# Power_Supply.net
KiCad netlist of a schematic drawn in EAGLE
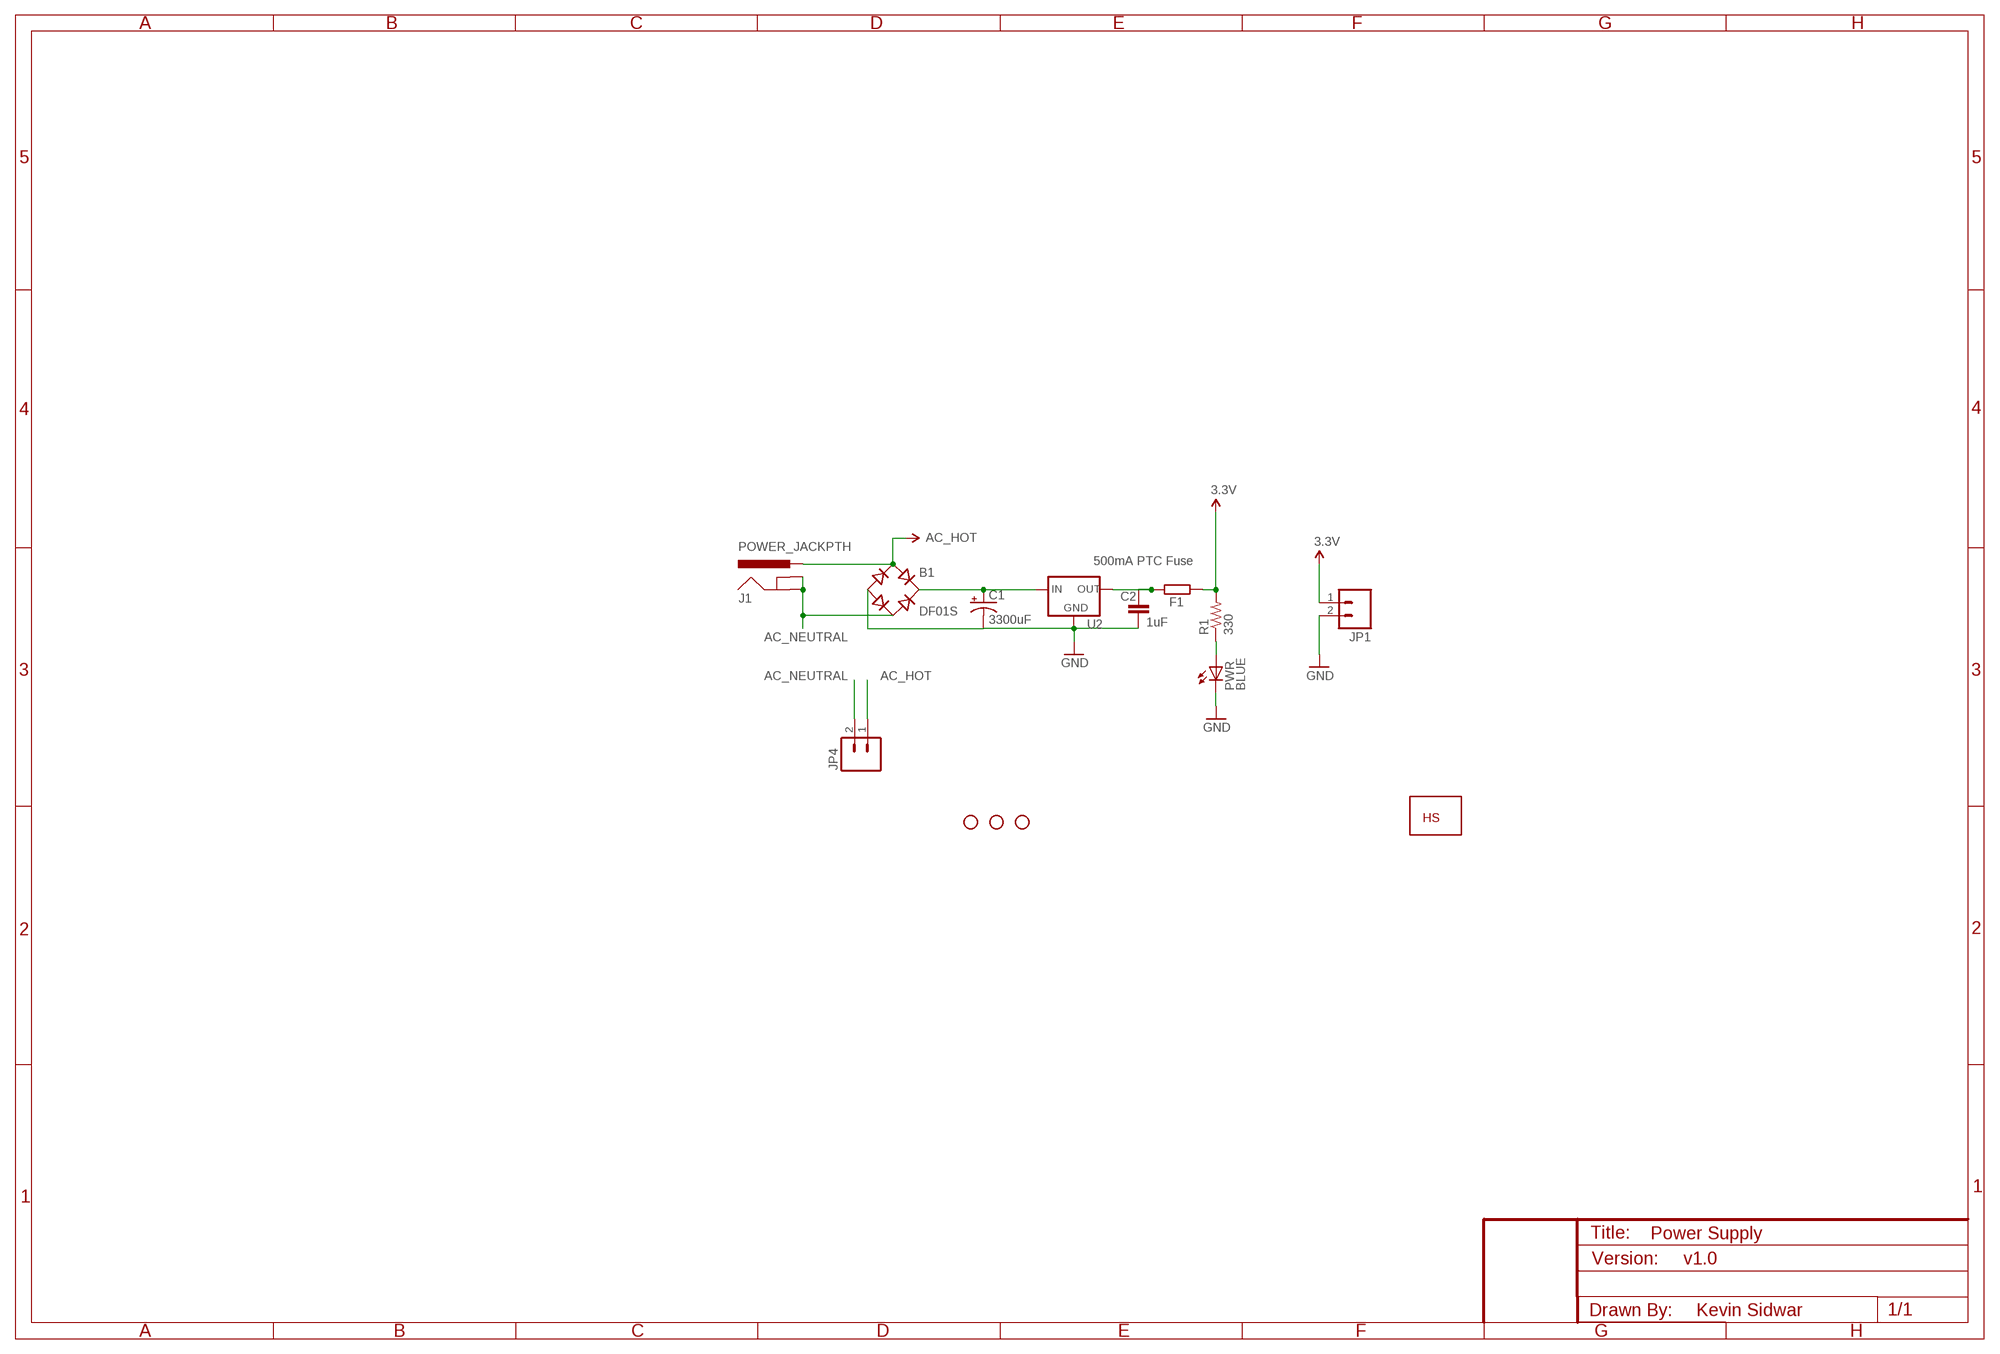
[diagram p0: schematic, sheet 1]

(export (version "E")
  (design (tool "Eeschema 10.0.6"))
  (components
    (comp (ref "B1")
      (value "DF01S")
      (footprint "eagle-import:DFS")
      (libsource (lib "eagle-import") (part "DFS01"))
    )
    (comp (ref "C1")
      (value "3300uF")
      (footprint "eagle-import:EB20D")
      (libsource (lib "eagle-import") (part "CPOL-USE10-20"))
    )
    (comp (ref "C2")
      (value "1uF")
      (footprint "eagle-import:0603-CAP")
      (libsource (lib "eagle-import") (part "CAP0603-CAP"))
    )
    (comp (ref "F1")
      (value "500mA PTC Fuse")
      (footprint "eagle-import:M1206")
      (libsource (lib "eagle-import") (part "R-EU_M1206"))
    )
    (comp (ref "J1")
      (value "POWER_JACKPTH")
      (footprint "eagle-import:POWER_JACK_PTH")
      (libsource (lib "eagle-import") (part "POWER_JACKPTH"))
    )
    (comp (ref "JP1")
      (value "M02LOCK_LONGPADS")
      (footprint "eagle-import:1X02_LOCK_LONGPADS")
      (libsource (lib "eagle-import") (part "M02LOCK_LONGPADS"))
    )
    (comp (ref "JP4")
      (value "M02LOCK_LONGPADS")
      (footprint "eagle-import:1X02_LOCK_LONGPADS")
      (libsource (lib "eagle-import") (part "M02LOCK_LONGPADS"))
    )
    (comp (ref "JP5")
      (value "STAND-OFF")
      (footprint "eagle-import:STAND-OFF")
      (libsource (lib "eagle-import") (part "STAND-OFF"))
    )
    (comp (ref "JP6")
      (value "STAND-OFF")
      (footprint "eagle-import:STAND-OFF")
      (libsource (lib "eagle-import") (part "STAND-OFF"))
    )
    (comp (ref "JP8")
      (value "STAND-OFF")
      (footprint "eagle-import:STAND-OFF")
      (libsource (lib "eagle-import") (part "STAND-OFF"))
    )
    (comp (ref "PWR")
      (value "BLUE")
      (footprint "eagle-import:LED-0603")
      (libsource (lib "eagle-import") (part "LED0603"))
    )
    (comp (ref "R1")
      (value "330")
      (footprint "eagle-import:0603-RES")
      (libsource (lib "eagle-import") (part "RESISTOR0603-RES"))
    )
    (comp (ref "U$1")
      (value "LOGONORMAL")
      (footprint "eagle-import:HS_LOGO")
      (libsource (lib "eagle-import") (part "LOGONORMAL"))
    )
    (comp (ref "U2")
      (value "RECOM_X.X_REG78XX")
      (footprint "eagle-import:RECOM")
      (libsource (lib "eagle-import") (part "RECOM_X.X_REG78XX"))
    )
  )
  (nets
    (net (code "1") (name "/AC_NEUTRAL") (class "Default")
      (node (ref "B1") (pin "AC2") (pinfunction "AC2_AC2") (pintype "passive"))
      (node (ref "J1") (pin "GND") (pinfunction "GND_GND") (pintype "bidirectional"))
      (node (ref "J1") (pin "GNDBREAK") (pinfunction "GNDBREAK_GNDBREAK") (pintype "bidirectional"))
      (node (ref "JP4") (pin "2") (pinfunction "2_2") (pintype "passive"))
    )
    (net (code "2") (name "3.3V") (class "Default")
      (node (ref "F1") (pin "1") (pinfunction "1_1") (pintype "passive"))
      (node (ref "JP1") (pin "1") (pinfunction "1_1") (pintype "passive"))
      (node (ref "R1") (pin "2") (pinfunction "2_2") (pintype "passive"))
    )
    (net (code "3") (name "AC_HOT") (class "Default")
      (node (ref "B1") (pin "AC1") (pinfunction "AC1_AC1") (pintype "passive"))
      (node (ref "J1") (pin "PWR") (pinfunction "PWR_PWR") (pintype "bidirectional"))
      (node (ref "JP4") (pin "1") (pinfunction "1_1") (pintype "passive"))
    )
    (net (code "4") (name "GND") (class "Default")
      (node (ref "B1") (pin "-") (pinfunction "-_-") (pintype "passive"))
      (node (ref "C1") (pin "-") (pinfunction "-_-") (pintype "passive"))
      (node (ref "C2") (pin "2") (pinfunction "2_2") (pintype "passive"))
      (node (ref "JP1") (pin "2") (pinfunction "2_2") (pintype "passive"))
      (node (ref "PWR") (pin "C") (pinfunction "C_C") (pintype "passive"))
      (node (ref "U2") (pin "GND") (pinfunction "GND_GND") (pintype "input"))
    )
    (net (code "5") (name "Net-(PWR-PadA)") (class "Default")
      (node (ref "PWR") (pin "A") (pinfunction "A_A") (pintype "passive"))
      (node (ref "R1") (pin "1") (pinfunction "1_1") (pintype "passive"))
    )
    (net (code "6") (name "Net-(U2-IN)") (class "Default")
      (node (ref "B1") (pin "+") (pinfunction "+_+") (pintype "passive"))
      (node (ref "C1") (pin "+") (pinfunction "+_+") (pintype "passive"))
      (node (ref "U2") (pin "VIN") (pinfunction "IN_VIN") (pintype "input"))
    )
    (net (code "7") (name "Net-(U2-OUT)") (class "Default")
      (node (ref "C2") (pin "1") (pinfunction "1_1") (pintype "passive"))
      (node (ref "F1") (pin "2") (pinfunction "2_2") (pintype "passive"))
      (node (ref "U2") (pin "VOUT") (pinfunction "OUT_VOUT") (pintype "output"))
    )
  )
)
